# 3_TopLevel.net
KiCad netlist of a schematic drawn in Altium Designer
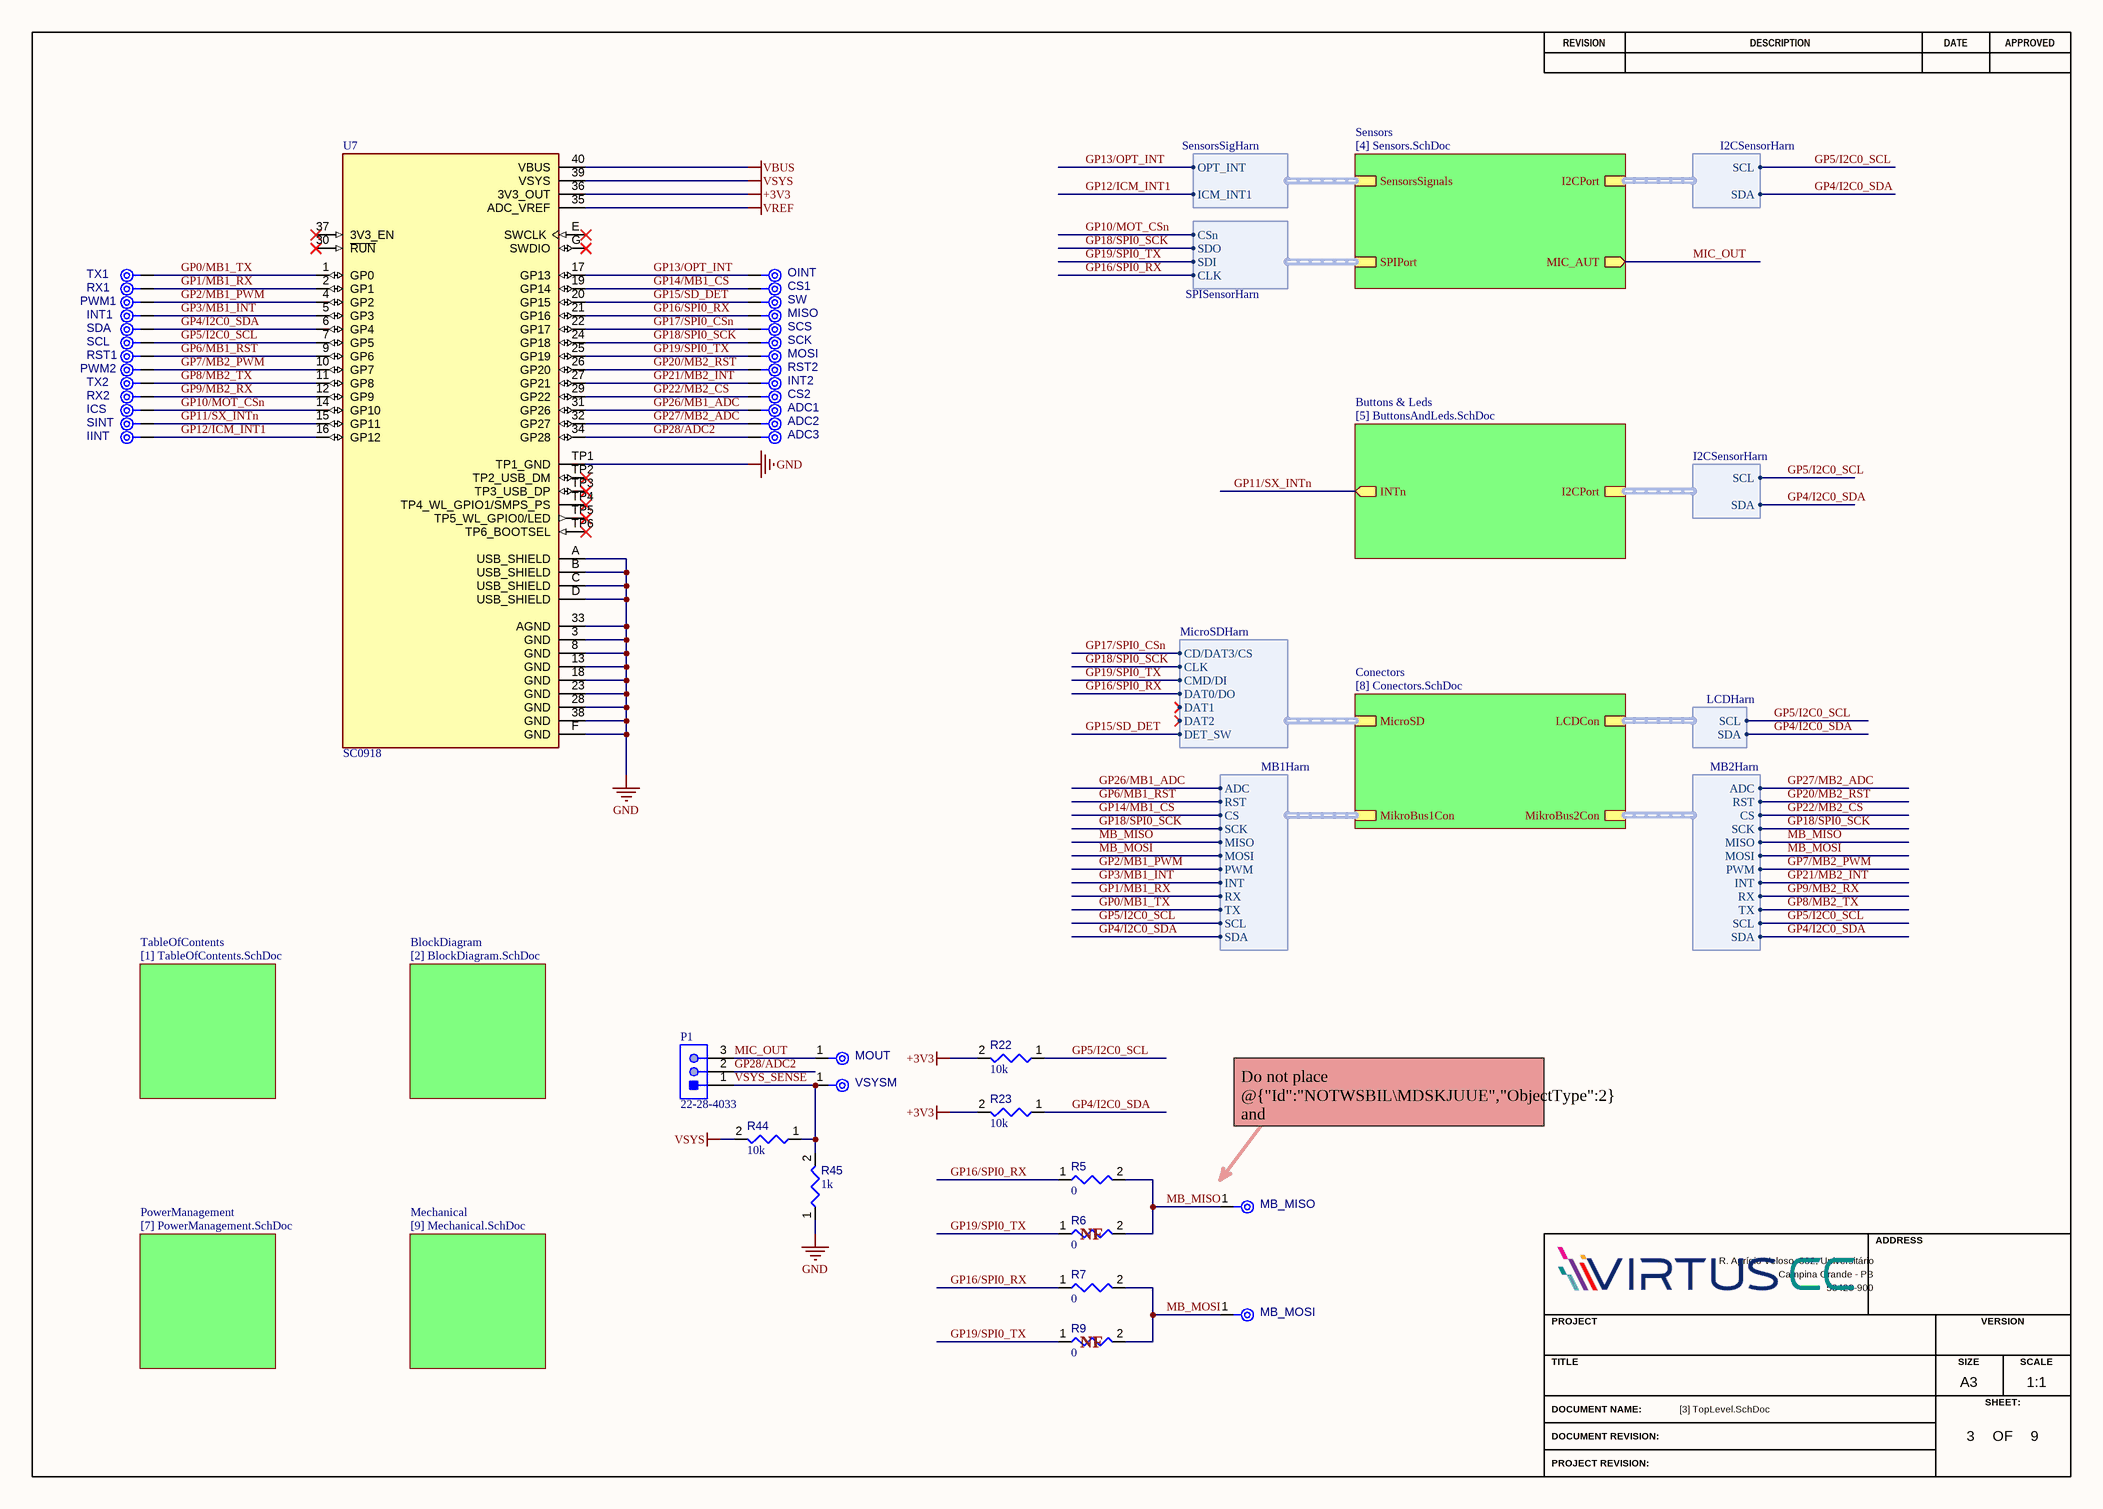
[diagram p0: [3] TopLevel.SchDoc]

(export (version "E")
  (design (tool "Eeschema 10.0.6"))
  (components
    (comp (ref "ADC1")
      (value "TPAD6R")
      (footprint "TP06R")
      (description "0.6mm round")
      (libsource (lib "") (part "CMP-001-0001-4_1"))
    )
    (comp (ref "ADC2")
      (value "TPAD6R")
      (footprint "TP06R")
      (description "0.6mm round")
      (libsource (lib "") (part "CMP-001-0001-4_1"))
    )
    (comp (ref "ADC3")
      (value "TPAD6R")
      (footprint "TP06R")
      (description "0.6mm round")
      (libsource (lib "") (part "CMP-001-0001-4_1"))
    )
    (comp (ref "CS1")
      (value "TPAD6R")
      (footprint "TP06R")
      (description "0.6mm round")
      (libsource (lib "") (part "CMP-001-0001-4_1"))
    )
    (comp (ref "CS2")
      (value "TPAD6R")
      (footprint "TP06R")
      (description "0.6mm round")
      (libsource (lib "") (part "CMP-001-0001-4_1"))
    )
    (comp (ref "ICS")
      (value "TPAD6R")
      (footprint "TP06R")
      (description "0.6mm round")
      (libsource (lib "") (part "CMP-001-0001-4_1"))
    )
    (comp (ref "IINT")
      (value "TPAD6R")
      (footprint "TP06R")
      (description "0.6mm round")
      (libsource (lib "") (part "CMP-001-0001-4_1"))
    )
    (comp (ref "INT1")
      (value "TPAD6R")
      (footprint "TP06R")
      (description "0.6mm round")
      (libsource (lib "") (part "CMP-001-0001-4_1"))
    )
    (comp (ref "INT2")
      (value "TPAD6R")
      (footprint "TP06R")
      (description "0.6mm round")
      (libsource (lib "") (part "CMP-001-0001-4_1"))
    )
    (comp (ref "MB_MISO")
      (value "TPAD6R")
      (footprint "TP06R")
      (description "0.6mm round")
      (libsource (lib "UFCG - Universidade Federal de Campina Grande") (part "CMP-001-0001-4"))
    )
    (comp (ref "MB_MOSI")
      (value "TPAD6R")
      (footprint "TP06R")
      (description "0.6mm round")
      (libsource (lib "UFCG - Universidade Federal de Campina Grande") (part "CMP-001-0001-4"))
    )
    (comp (ref "MISO")
      (value "TPAD6R")
      (footprint "TP06R")
      (description "0.6mm round")
      (libsource (lib "") (part "CMP-001-0001-4_1"))
    )
    (comp (ref "MOSI")
      (value "TPAD6R")
      (footprint "TP06R")
      (description "0.6mm round")
      (libsource (lib "") (part "CMP-001-0001-4_1"))
    )
    (comp (ref "MOUT")
      (value "TPAD6R")
      (footprint "TP06R")
      (description "0.6mm round")
      (libsource (lib "UFCG - Universidade Federal de Campina Grande") (part "CMP-001-0001-4"))
    )
    (comp (ref "OINT")
      (value "TPAD6R")
      (footprint "TP06R")
      (description "0.6mm round")
      (libsource (lib "") (part "CMP-001-0001-4_1"))
    )
    (comp (ref "P1")
      (value "22-28-4033")
      (footprint "MOLX-22-28-4033_V")
      (description "KK 254 Breakaway Header Vertical 3 Circuits 0.38um Gold Selective Plating Mating Pin 6.09mm")
      (libsource (lib "UFCG - Universidade Federal de Campina Grande") (part "CN-1P-M-R3"))
    )
    (comp (ref "PWM1")
      (value "TPAD6R")
      (footprint "TP06R")
      (description "0.6mm round")
      (libsource (lib "") (part "CMP-001-0001-4_1"))
    )
    (comp (ref "PWM2")
      (value "TPAD6R")
      (footprint "TP06R")
      (description "0.6mm round")
      (libsource (lib "") (part "CMP-001-0001-4_1"))
    )
    (comp (ref "R5")
      (value "0")
      (footprint "RESC0603(1608)_L")
      (description "Chip Resistor, 0 Ohm, 0.1 W, -55 to 155 degC, 0603 (1608 Metric)")
      (fields (field (name "TOLERANCE") "5%") (field (name "POWER") "100mW"))
      (libsource (lib "UFCG - Universidade Federal de Campina Grande") (part "RES-2"))
    )
    (comp (ref "R6")
      (value "0")
      (footprint "RESC0603(1608)_L")
      (description "Chip Resistor, 0 Ohm, 0.1 W, -55 to 155 degC, 0603 (1608 Metric)")
      (fields (field (name "TOLERANCE") "5%") (field (name "POWER") "100mW"))
      (libsource (lib "UFCG - Universidade Federal de Campina Grande") (part "RES-2"))
    )
    (comp (ref "R7")
      (value "0")
      (footprint "RESC0603(1608)_L")
      (description "Chip Resistor, 0 Ohm, 0.1 W, -55 to 155 degC, 0603 (1608 Metric)")
      (fields (field (name "TOLERANCE") "5%") (field (name "POWER") "100mW"))
      (libsource (lib "UFCG - Universidade Federal de Campina Grande") (part "RES-2"))
    )
    (comp (ref "R9")
      (value "0")
      (footprint "RESC0603(1608)_L")
      (description "Chip Resistor, 0 Ohm, 0.1 W, -55 to 155 degC, 0603 (1608 Metric)")
      (fields (field (name "TOLERANCE") "5%") (field (name "POWER") "100mW"))
      (libsource (lib "UFCG - Universidade Federal de Campina Grande") (part "RES-2"))
    )
    (comp (ref "R22")
      (value "10k")
      (footprint "RESC0603(1608)_L")
      (description "Chip Resistor, 10 KOhm, +/- 1%, 01 W, -55 to 155 degC, 0603 (1608 Metric)")
      (fields (field (name "POWER") "100mW") (field (name "TOLERANCE") "1%"))
      (libsource (lib "UFCG - Universidade Federal de Campina Grande") (part "RES-2"))
    )
    (comp (ref "R23")
      (value "10k")
      (footprint "RESC0603(1608)_L")
      (description "Chip Resistor, 10 KOhm, +/- 1%, 01 W, -55 to 155 degC, 0603 (1608 Metric)")
      (fields (field (name "POWER") "100mW") (field (name "TOLERANCE") "1%"))
      (libsource (lib "UFCG - Universidade Federal de Campina Grande") (part "RES-2"))
    )
    (comp (ref "R44")
      (value "10k")
      (footprint "RESC0603(1608)_L")
      (description "Chip Resistor, 10 KOhm, +/- 1%, 01 W, -55 to 155 degC, 0603 (1608 Metric)")
      (fields (field (name "POWER") "100mW") (field (name "TOLERANCE") "1%"))
      (libsource (lib "UFCG - Universidade Federal de Campina Grande") (part "RES-2"))
    )
    (comp (ref "R45")
      (value "1k")
      (footprint "RESC0603(1608)_L")
      (description "Chip Resistor, 1 KOhm, +/-1%, 0.1 W, -55 to 155 degC, 0603 (1608 Metric)")
      (fields (field (name "POWER") "100mW") (field (name "TOLERANCE") "1%"))
      (libsource (lib "UFCG - Universidade Federal de Campina Grande") (part "RES-2"))
    )
    (comp (ref "RST1")
      (value "TPAD6R")
      (footprint "TP06R")
      (description "0.6mm round")
      (libsource (lib "") (part "CMP-001-0001-4_1"))
    )
    (comp (ref "RST2")
      (value "TPAD6R")
      (footprint "TP06R")
      (description "0.6mm round")
      (libsource (lib "") (part "CMP-001-0001-4_1"))
    )
    (comp (ref "RX1")
      (value "TPAD6R")
      (footprint "TP06R")
      (description "0.6mm round")
      (libsource (lib "") (part "CMP-001-0001-4_1"))
    )
    (comp (ref "RX2")
      (value "TPAD6R")
      (footprint "TP06R")
      (description "0.6mm round")
      (libsource (lib "") (part "CMP-001-0001-4_1"))
    )
    (comp (ref "SCK")
      (value "TPAD6R")
      (footprint "TP06R")
      (description "0.6mm round")
      (libsource (lib "") (part "CMP-001-0001-4_1"))
    )
    (comp (ref "SCL")
      (value "TPAD6R")
      (footprint "TP06R")
      (description "0.6mm round")
      (libsource (lib "") (part "CMP-001-0001-4_1"))
    )
    (comp (ref "SCS")
      (value "TPAD6R")
      (footprint "TP06R")
      (description "0.6mm round")
      (libsource (lib "") (part "CMP-001-0001-4_1"))
    )
    (comp (ref "SDA")
      (value "TPAD6R")
      (footprint "TP06R")
      (description "0.6mm round")
      (libsource (lib "") (part "CMP-001-0001-4_1"))
    )
    (comp (ref "SINT")
      (value "TPAD6R")
      (footprint "TP06R")
      (description "0.6mm round")
      (libsource (lib "") (part "CMP-001-0001-4_1"))
    )
    (comp (ref "SW")
      (value "TPAD6R")
      (footprint "TP06R")
      (description "0.6mm round")
      (libsource (lib "") (part "CMP-001-0001-4_1"))
    )
    (comp (ref "TX1")
      (value "TPAD6R")
      (footprint "TP06R")
      (description "0.6mm round")
      (libsource (lib "") (part "CMP-001-0001-4_1"))
    )
    (comp (ref "TX2")
      (value "TPAD6R")
      (footprint "TP06R")
      (description "0.6mm round")
      (libsource (lib "") (part "CMP-001-0001-4_1"))
    )
    (comp (ref "U7")
      (value "SC0918")
      (footprint "MODULE_SC0918")
      (description "Raspberry Pi Pico W RP2040")
      (fields (field (name "MF") "Raspberry Pi"))
      (libsource (lib "UFCG - Universidade Federal de Campina Grande") (part "SC0918"))
    )
    (comp (ref "VSYSM")
      (value "TPAD6R")
      (footprint "TP06R")
      (description "0.6mm round")
      (libsource (lib "UFCG - Universidade Federal de Campina Grande") (part "CMP-001-0001-4"))
    )
  )
  (nets
    (net (code "8") (name "+3V3") (class "Default")
      (node (ref "R22") (pin "2") (pinfunction "2_2") (pintype "passive"))
      (node (ref "R23") (pin "2") (pinfunction "2_2") (pintype "passive"))
      (node (ref "U7") (pin "36") (pinfunction "3V3_OUT_36") (pintype "power_in"))
    )
    (net (code "9") (name "/GP0{slash}MB1_TX") (class "Default")
      (node (ref "TX1") (pin "1") (pinfunction "TP_1") (pintype "passive"))
      (node (ref "U7") (pin "1") (pinfunction "GP0_1") (pintype "bidirectional"))
    )
    (net (code "10") (name "/GP1{slash}MB1_RX") (class "Default")
      (node (ref "RX1") (pin "1") (pinfunction "TP_1") (pintype "passive"))
      (node (ref "U7") (pin "2") (pinfunction "GP1_2") (pintype "bidirectional"))
    )
    (net (code "11") (name "/GP2{slash}MB1_PWM") (class "Default")
      (node (ref "PWM1") (pin "1") (pinfunction "TP_1") (pintype "passive"))
      (node (ref "U7") (pin "4") (pinfunction "GP2_4") (pintype "bidirectional"))
    )
    (net (code "12") (name "/GP3{slash}MB1_INT") (class "Default")
      (node (ref "INT1") (pin "1") (pinfunction "TP_1") (pintype "passive"))
      (node (ref "U7") (pin "5") (pinfunction "GP3_5") (pintype "bidirectional"))
    )
    (net (code "13") (name "/GP4{slash}I2C0_SDA") (class "Default")
      (node (ref "R23") (pin "1") (pinfunction "1_1") (pintype "passive"))
      (node (ref "SDA") (pin "1") (pinfunction "TP_1") (pintype "passive"))
      (node (ref "U7") (pin "6") (pinfunction "GP4_6") (pintype "bidirectional"))
    )
    (net (code "14") (name "/GP5{slash}I2C0_SCL") (class "Default")
      (node (ref "R22") (pin "1") (pinfunction "1_1") (pintype "passive"))
      (node (ref "SCL") (pin "1") (pinfunction "TP_1") (pintype "passive"))
      (node (ref "U7") (pin "7") (pinfunction "GP5_7") (pintype "bidirectional"))
    )
    (net (code "15") (name "/GP6{slash}MB1_RST") (class "Default")
      (node (ref "RST1") (pin "1") (pinfunction "TP_1") (pintype "passive"))
      (node (ref "U7") (pin "9") (pinfunction "GP6_9") (pintype "bidirectional"))
    )
    (net (code "16") (name "/GP7{slash}MB2_PWM") (class "Default")
      (node (ref "PWM2") (pin "1") (pinfunction "TP_1") (pintype "passive"))
      (node (ref "U7") (pin "10") (pinfunction "GP7_10") (pintype "bidirectional"))
    )
    (net (code "17") (name "/GP8{slash}MB2_TX") (class "Default")
      (node (ref "TX2") (pin "1") (pinfunction "TP_1") (pintype "passive"))
      (node (ref "U7") (pin "11") (pinfunction "GP8_11") (pintype "bidirectional"))
    )
    (net (code "18") (name "/GP9{slash}MB2_RX") (class "Default")
      (node (ref "RX2") (pin "1") (pinfunction "TP_1") (pintype "passive"))
      (node (ref "U7") (pin "12") (pinfunction "GP9_12") (pintype "bidirectional"))
    )
    (net (code "19") (name "/GP10{slash}MOT_CSn") (class "Default")
      (node (ref "ICS") (pin "1") (pinfunction "TP_1") (pintype "passive"))
      (node (ref "U7") (pin "14") (pinfunction "GP10_14") (pintype "bidirectional"))
    )
    (net (code "20") (name "/GP11{slash}SX_INTn") (class "Default")
      (node (ref "SINT") (pin "1") (pinfunction "TP_1") (pintype "passive"))
      (node (ref "U7") (pin "15") (pinfunction "GP11_15") (pintype "bidirectional"))
    )
    (net (code "21") (name "/GP12{slash}ICM_INT1") (class "Default")
      (node (ref "IINT") (pin "1") (pinfunction "TP_1") (pintype "passive"))
      (node (ref "U7") (pin "16") (pinfunction "GP12_16") (pintype "bidirectional"))
    )
    (net (code "22") (name "/GP13{slash}OPT_INT") (class "Default")
      (node (ref "OINT") (pin "1") (pinfunction "TP_1") (pintype "passive"))
      (node (ref "U7") (pin "17") (pinfunction "GP13_17") (pintype "bidirectional"))
    )
    (net (code "23") (name "/GP14{slash}MB1_CS") (class "Default")
      (node (ref "CS1") (pin "1") (pinfunction "TP_1") (pintype "passive"))
      (node (ref "U7") (pin "19") (pinfunction "GP14_19") (pintype "bidirectional"))
    )
    (net (code "24") (name "/GP15{slash}SD_DET") (class "Default")
      (node (ref "SW") (pin "1") (pinfunction "TP_1") (pintype "passive"))
      (node (ref "U7") (pin "20") (pinfunction "GP15_20") (pintype "bidirectional"))
    )
    (net (code "25") (name "/GP16{slash}SPI0_RX") (class "Default")
      (node (ref "MISO") (pin "1") (pinfunction "TP_1") (pintype "passive"))
      (node (ref "R5") (pin "1") (pinfunction "1_1") (pintype "passive"))
      (node (ref "R7") (pin "1") (pinfunction "1_1") (pintype "passive"))
      (node (ref "U7") (pin "21") (pinfunction "GP16_21") (pintype "bidirectional"))
    )
    (net (code "26") (name "/GP17{slash}SPI0_CSn") (class "Default")
      (node (ref "SCS") (pin "1") (pinfunction "TP_1") (pintype "passive"))
      (node (ref "U7") (pin "22") (pinfunction "GP17_22") (pintype "bidirectional"))
    )
    (net (code "27") (name "/GP18{slash}SPI0_SCK") (class "Default")
      (node (ref "SCK") (pin "1") (pinfunction "TP_1") (pintype "passive"))
      (node (ref "U7") (pin "24") (pinfunction "GP18_24") (pintype "bidirectional"))
    )
    (net (code "28") (name "/GP19{slash}SPI0_TX") (class "Default")
      (node (ref "MOSI") (pin "1") (pinfunction "TP_1") (pintype "passive"))
      (node (ref "R6") (pin "1") (pinfunction "1_1") (pintype "passive"))
      (node (ref "R9") (pin "1") (pinfunction "1_1") (pintype "passive"))
      (node (ref "U7") (pin "25") (pinfunction "GP19_25") (pintype "bidirectional"))
    )
    (net (code "29") (name "/GP20{slash}MB2_RST") (class "Default")
      (node (ref "RST2") (pin "1") (pinfunction "TP_1") (pintype "passive"))
      (node (ref "U7") (pin "26") (pinfunction "GP20_26") (pintype "bidirectional"))
    )
    (net (code "30") (name "/GP21{slash}MB2_INT") (class "Default")
      (node (ref "INT2") (pin "1") (pinfunction "TP_1") (pintype "passive"))
      (node (ref "U7") (pin "27") (pinfunction "GP21_27") (pintype "bidirectional"))
    )
    (net (code "31") (name "/GP22{slash}MB2_CS") (class "Default")
      (node (ref "CS2") (pin "1") (pinfunction "TP_1") (pintype "passive"))
      (node (ref "U7") (pin "29") (pinfunction "GP22_29") (pintype "bidirectional"))
    )
    (net (code "32") (name "/GP26{slash}MB1_ADC") (class "Default")
      (node (ref "ADC1") (pin "1") (pinfunction "TP_1") (pintype "passive"))
      (node (ref "U7") (pin "31") (pinfunction "GP26_31") (pintype "bidirectional"))
    )
    (net (code "33") (name "/GP27{slash}MB2_ADC") (class "Default")
      (node (ref "ADC2") (pin "1") (pinfunction "TP_1") (pintype "passive"))
      (node (ref "U7") (pin "32") (pinfunction "GP27_32") (pintype "bidirectional"))
    )
    (net (code "34") (name "/GP28{slash}ADC2") (class "Default")
      (node (ref "ADC3") (pin "1") (pinfunction "TP_1") (pintype "passive"))
      (node (ref "P1") (pin "2") (pinfunction "2_2") (pintype "passive"))
      (node (ref "U7") (pin "34") (pinfunction "GP28_34") (pintype "bidirectional"))
    )
    (net (code "35") (name "/MB_MISO") (class "Default")
      (node (ref "MB_MISO") (pin "1") (pinfunction "TP_1") (pintype "passive"))
      (node (ref "R5") (pin "2") (pinfunction "2_2") (pintype "passive"))
      (node (ref "R6") (pin "2") (pinfunction "2_2") (pintype "passive"))
    )
    (net (code "36") (name "/MB_MOSI") (class "Default")
      (node (ref "MB_MOSI") (pin "1") (pinfunction "TP_1") (pintype "passive"))
      (node (ref "R7") (pin "2") (pinfunction "2_2") (pintype "passive"))
      (node (ref "R9") (pin "2") (pinfunction "2_2") (pintype "passive"))
    )
    (net (code "37") (name "/MIC_OUT") (class "Default")
      (node (ref "MOUT") (pin "1") (pinfunction "TP_1") (pintype "passive"))
      (node (ref "P1") (pin "3") (pinfunction "3_3") (pintype "passive"))
    )
    (net (code "38") (name "/VSYS_SENSE") (class "Default")
      (node (ref "P1") (pin "1") (pinfunction "1_1") (pintype "passive"))
      (node (ref "R44") (pin "1") (pinfunction "1_1") (pintype "passive"))
      (node (ref "R45") (pin "2") (pinfunction "2_2") (pintype "passive"))
      (node (ref "VSYSM") (pin "1") (pinfunction "TP_1") (pintype "passive"))
    )
    (net (code "46") (name "GND") (class "Default")
      (node (ref "R45") (pin "1") (pinfunction "1_1") (pintype "passive"))
      (node (ref "U7") (pin "13") (pinfunction "GND_13") (pintype "power_in"))
      (node (ref "U7") (pin "18") (pinfunction "GND_18") (pintype "power_in"))
      (node (ref "U7") (pin "23") (pinfunction "GND_23") (pintype "power_in"))
      (node (ref "U7") (pin "28") (pinfunction "GND_28") (pintype "power_in"))
      (node (ref "U7") (pin "3") (pinfunction "GND_3") (pintype "power_in"))
      (node (ref "U7") (pin "33") (pinfunction "AGND_33") (pintype "power_in"))
      (node (ref "U7") (pin "38") (pinfunction "GND_38") (pintype "power_in"))
      (node (ref "U7") (pin "8") (pinfunction "GND_8") (pintype "power_in"))
      (node (ref "U7") (pin "A") (pinfunction "USB_SHIELD_A") (pintype "power_in"))
      (node (ref "U7") (pin "B") (pinfunction "USB_SHIELD_B") (pintype "power_in"))
      (node (ref "U7") (pin "C") (pinfunction "USB_SHIELD_C") (pintype "power_in"))
      (node (ref "U7") (pin "D") (pinfunction "USB_SHIELD_D") (pintype "power_in"))
      (node (ref "U7") (pin "F") (pinfunction "GND_F") (pintype "power_in"))
      (node (ref "U7") (pin "TP1") (pinfunction "TP1_GND_TP1") (pintype "power_in"))
    )
    (net (code "47") (name "VBUS") (class "Default")
      (node (ref "U7") (pin "40") (pinfunction "VBUS_40") (pintype "power_in"))
    )
    (net (code "48") (name "VREF") (class "Default")
      (node (ref "U7") (pin "35") (pinfunction "ADC_VREF_35") (pintype "power_in"))
    )
    (net (code "49") (name "VSYS") (class "Default")
      (node (ref "R44") (pin "2") (pinfunction "2_2") (pintype "passive"))
      (node (ref "U7") (pin "39") (pinfunction "VSYS_39") (pintype "power_in"))
    )
    (net (code "50") (name "unconnected-(U7-3V3_EN-Pad37)") (class "Default")
      (node (ref "U7") (pin "37") (pinfunction "3V3_EN_37") (pintype "input+no_connect"))
    )
    (net (code "51") (name "unconnected-(U7-SWCLK-PadE)") (class "Default")
      (node (ref "U7") (pin "E") (pinfunction "SWCLK_E") (pintype "input+no_connect"))
    )
    (net (code "52") (name "unconnected-(U7-SWDIO-PadG)") (class "Default")
      (node (ref "U7") (pin "G") (pinfunction "SWDIO_G") (pintype "bidirectional+no_connect"))
    )
    (net (code "53") (name "unconnected-(U7-TP2_USB_DM-PadTP2)") (class "Default")
      (node (ref "U7") (pin "TP2") (pinfunction "TP2_USB_DM_TP2") (pintype "bidirectional+no_connect"))
    )
    (net (code "54") (name "unconnected-(U7-TP3_USB_DP-PadTP3)") (class "Default")
      (node (ref "U7") (pin "TP3") (pinfunction "TP3_USB_DP_TP3") (pintype "bidirectional+no_connect"))
    )
    (net (code "55") (name "unconnected-(U7-TP4_WL_GPIO1{slash}SMPS_PS-PadTP4)") (class "Default")
      (node (ref "U7") (pin "TP4") (pinfunction "TP4_WL_GPIO1/SMPS_PS_TP4") (pintype "passive+no_connect"))
    )
    (net (code "56") (name "unconnected-(U7-TP5_WL_GPIO0{slash}LED-PadTP5)") (class "Default")
      (node (ref "U7") (pin "TP5") (pinfunction "TP5_WL_GPIO0/LED_TP5") (pintype "output+no_connect"))
    )
    (net (code "57") (name "unconnected-(U7-TP6_BOOTSEL-PadTP6)") (class "Default")
      (node (ref "U7") (pin "TP6") (pinfunction "TP6_BOOTSEL_TP6") (pintype "input+no_connect"))
    )
    (net (code "58") (name "unconnected-(U7-~{RUN}-Pad30)") (class "Default")
      (node (ref "U7") (pin "30") (pinfunction "~{RUN}_30") (pintype "input+no_connect"))
    )
  )
)
